# bitsClassicEdit.net
KiCad netlist of a schematic drawn in EAGLE
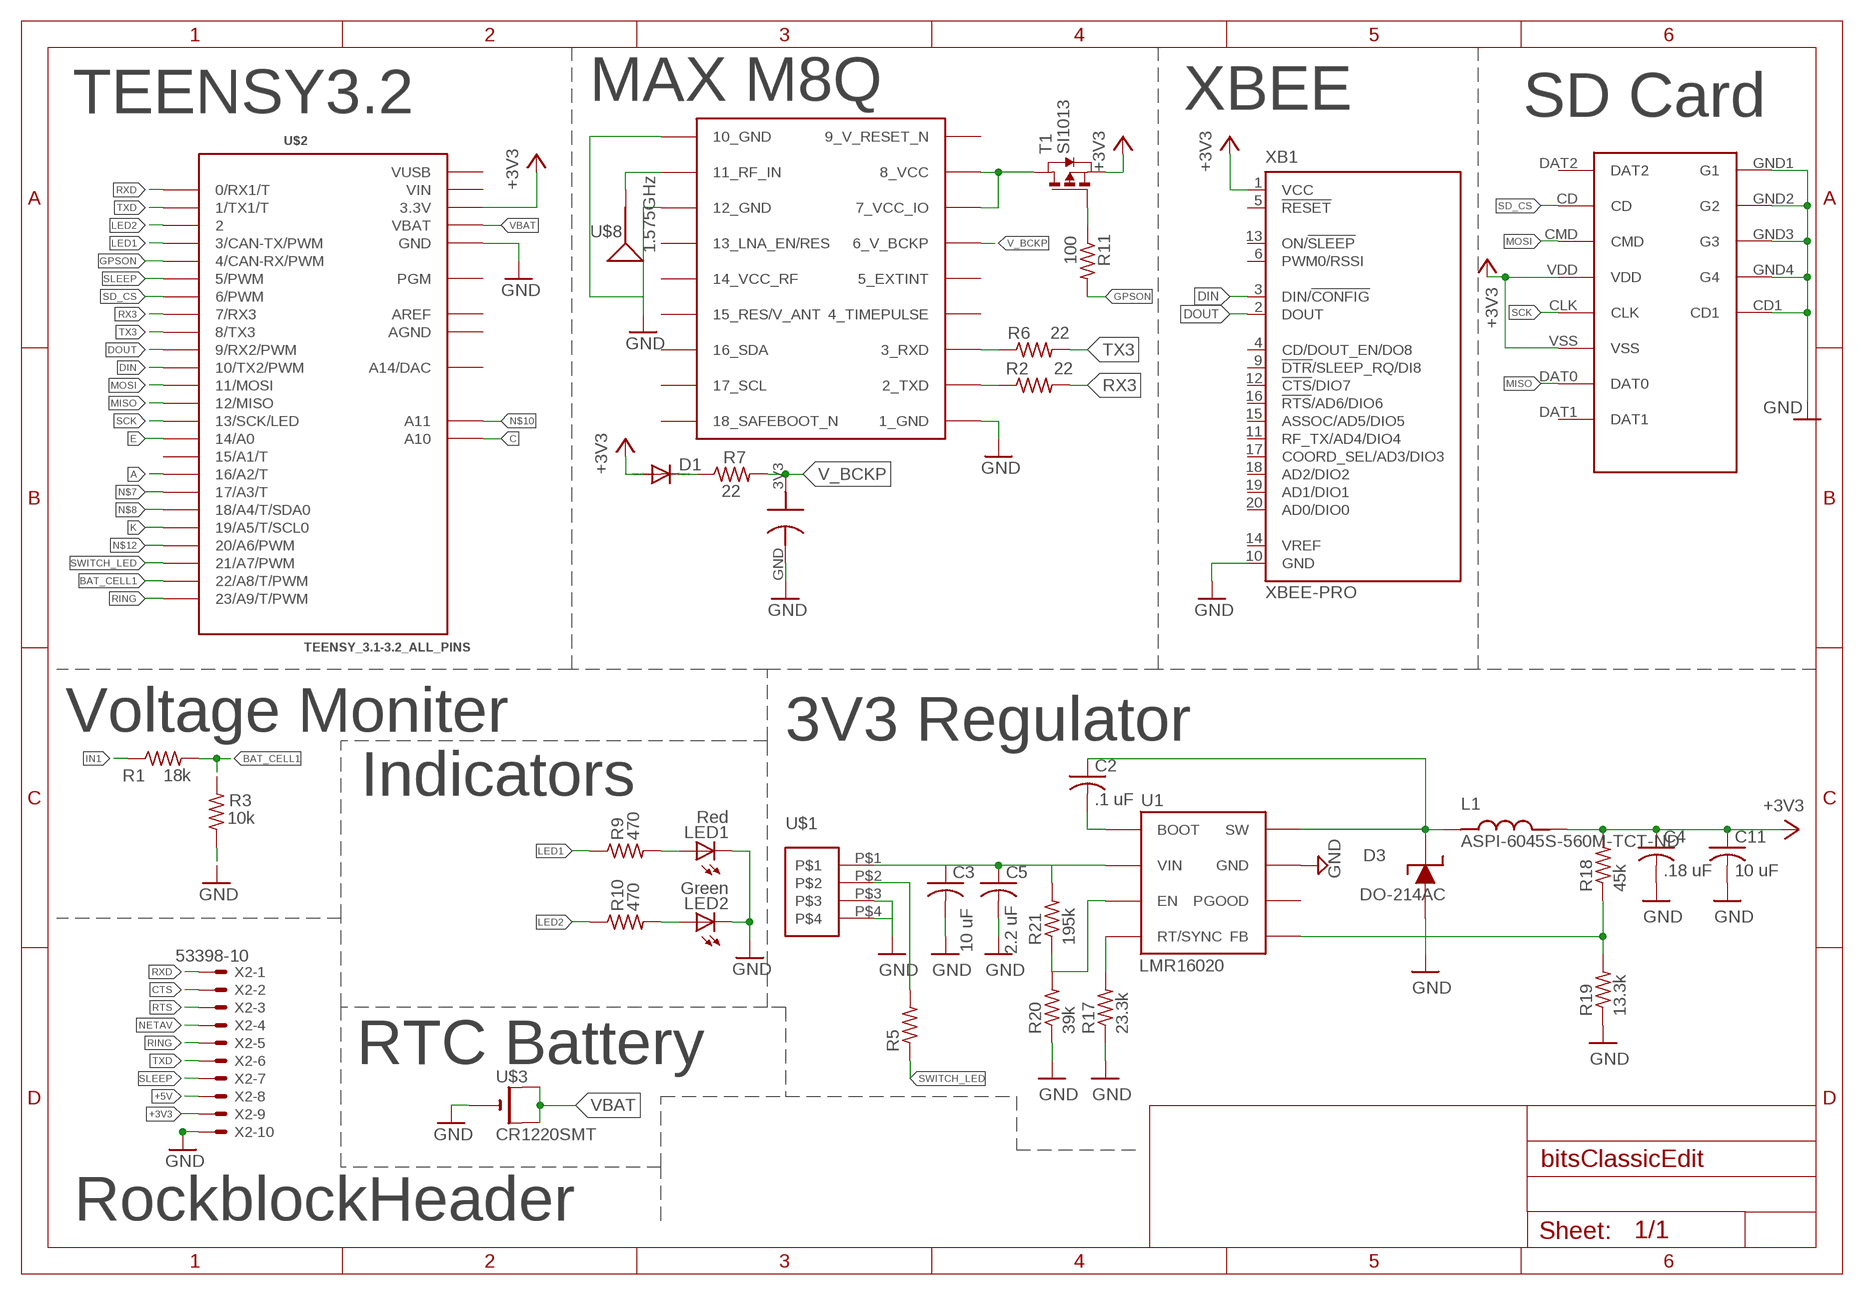
[diagram p0: schematic, sheet 1]

(export (version "E")
  (design (tool "Eeschema 10.0.6"))
  (components
    (comp (ref "C1")
      (value "DCK-3R3E204T614-E")
      (footprint "eagle-import:ELNASUPERCAP")
      (libsource (lib "eagle-import") (part "DCK-3R3E204T614-E"))
    )
    (comp (ref "C2")
      (value ".1 uF")
      (footprint "eagle-import:C0603")
      (libsource (lib "eagle-import") (part "C-USC0603"))
    )
    (comp (ref "C3")
      (value "10 uF")
      (footprint "eagle-import:C1210")
      (libsource (lib "eagle-import") (part "C-USC1210"))
    )
    (comp (ref "C4")
      (value ".18 uF")
      (footprint "eagle-import:C0603")
      (libsource (lib "eagle-import") (part "C-USC0603"))
    )
    (comp (ref "C5")
      (value "2.2 uF")
      (footprint "eagle-import:C1210")
      (libsource (lib "eagle-import") (part "C-USC1210"))
    )
    (comp (ref "C11")
      (value "10 uF")
      (footprint "eagle-import:C0603")
      (libsource (lib "eagle-import") (part "C-USC0603"))
    )
    (comp (ref "D1")
      (value "DIODE-SOD523")
      (footprint "eagle-import:SOD523")
      (libsource (lib "eagle-import") (part "DIODE-SOD523"))
    )
    (comp (ref "D3")
      (value "DO-214AC")
      (footprint "eagle-import:DO-214AC")
      (libsource (lib "eagle-import") (part "DO-214AC"))
    )
    (comp (ref "L1")
      (value "ASPI-6045S-560M-TCT-ND")
      (footprint "eagle-import:ABRACON")
      (libsource (lib "eagle-import") (part "ASPI-6045S-560M-TCT-ND"))
    )
    (comp (ref "LED1")
      (value "Red")
      (footprint "eagle-import:CHIP-LED0603")
      (libsource (lib "eagle-import") (part "LEDCHIP-LED0603"))
    )
    (comp (ref "LED2")
      (value "Green")
      (footprint "eagle-import:CHIP-LED0603")
      (libsource (lib "eagle-import") (part "LEDCHIP-LED0603"))
    )
    (comp (ref "R1")
      (value "18k")
      (footprint "eagle-import:R0603")
      (libsource (lib "eagle-import") (part "resistor_R-US_R0603"))
    )
    (comp (ref "R2")
      (value "22")
      (footprint "eagle-import:R0603")
      (libsource (lib "eagle-import") (part "R-US_R0603"))
    )
    (comp (ref "R3")
      (value "10k")
      (footprint "eagle-import:R0603")
      (libsource (lib "eagle-import") (part "resistor_R-US_R0603"))
    )
    (comp (ref "R5")
      (value "R-US_R0603")
      (footprint "eagle-import:R0603")
      (libsource (lib "eagle-import") (part "resistor_R-US_R0603"))
    )
    (comp (ref "R6")
      (value "22")
      (footprint "eagle-import:R0603")
      (libsource (lib "eagle-import") (part "R-US_R0603"))
    )
    (comp (ref "R7")
      (value "22")
      (footprint "eagle-import:R0603")
      (libsource (lib "eagle-import") (part "R-US_R0603"))
    )
    (comp (ref "R9")
      (value "470")
      (footprint "eagle-import:R0603")
      (libsource (lib "eagle-import") (part "resistor_R-US_R0603"))
    )
    (comp (ref "R10")
      (value "470")
      (footprint "eagle-import:R0603")
      (libsource (lib "eagle-import") (part "resistor_R-US_R0603"))
    )
    (comp (ref "R11")
      (value "100")
      (footprint "eagle-import:R0603")
      (libsource (lib "eagle-import") (part "R-US_R0603"))
    )
    (comp (ref "R17")
      (value "23.3k")
      (footprint "eagle-import:R0603")
      (libsource (lib "eagle-import") (part "resistor_R-US_R0603"))
    )
    (comp (ref "R18")
      (value "45k")
      (footprint "eagle-import:R0603")
      (libsource (lib "eagle-import") (part "resistor_R-US_R0603"))
    )
    (comp (ref "R19")
      (value "13.3k")
      (footprint "eagle-import:R0603")
      (libsource (lib "eagle-import") (part "resistor_R-US_R0603"))
    )
    (comp (ref "R20")
      (value "39k")
      (footprint "eagle-import:R0603")
      (libsource (lib "eagle-import") (part "resistor_R-US_R0603"))
    )
    (comp (ref "R21")
      (value "195k")
      (footprint "eagle-import:R0603")
      (libsource (lib "eagle-import") (part "resistor_R-US_R0603"))
    )
    (comp (ref "T1")
      (value "SI1013")
      (footprint "eagle-import:SC-75")
      (libsource (lib "eagle-import") (part "SI1013"))
    )
    (comp (ref "U$1")
      (value "MICROCLASP_4")
      (footprint "eagle-import:4_PIN_MICROCLASP")
      (libsource (lib "eagle-import") (part "MICROCLASP_4"))
    )
    (comp (ref "U$2")
      (value "TEENSY_3.1-3.2_ALL_PINS")
      (footprint "eagle-import:TEENSY_3.0-3.2&LC_ALL_PINS")
      (libsource (lib "eagle-import") (part "TEENSY_3.1-3.2_ALL_PINS"))
    )
    (comp (ref "U$3")
      (value "CR1220SMT")
      (footprint "eagle-import:CR1220-SMD")
      (libsource (lib "eagle-import") (part "CR1220SMT"))
    )
    (comp (ref "U$4")
      (value "MICRO_SD")
      (footprint "eagle-import:MICRO_SD_HINGED")
      (libsource (lib "eagle-import") (part "MICRO_SD"))
    )
    (comp (ref "U$7")
      (value "MAX-M8")
      (footprint "eagle-import:MAX-M8")
      (libsource (lib "eagle-import") (part "MAX-M8"))
    )
    (comp (ref "U$8")
      (value "1.575GHz")
      (footprint "eagle-import:SPARKFUN-GPS_ANT-GPS-2X7MM")
      (libsource (lib "eagle-import") (part "SPARKFUN-GPS_ANTENNAGPS-2X7MM"))
    )
    (comp (ref "U1")
      (value "LMR16020")
      (footprint "eagle-import:SO8")
      (libsource (lib "eagle-import") (part "LMR16020"))
    )
    (comp (ref "X2")
      (value "53398-10")
      (footprint "eagle-import:53398-10")
      (fields (field (name "MF") "MOLEX") (field (name "MPN") "53398-1071"))
      (libsource (lib "eagle-import") (part "53?-10398"))
    )
    (comp (ref "XB1")
      (value "XBEE-PRO")
      (footprint "eagle-import:XBEE-PRO")
      (fields (field (name "MPN") "XBP24-AWI-001"))
      (libsource (lib "eagle-import") (part "XBEE-PRO"))
    )
  )
  (nets
    (net (code "1") (name "+3V3") (class "Default")
      (node (ref "C11") (pin "1") (pinfunction "1_1") (pintype "passive"))
      (node (ref "C4") (pin "1") (pinfunction "1_1") (pintype "passive"))
      (node (ref "D1") (pin "A") (pinfunction "A_A") (pintype "passive"))
      (node (ref "L1") (pin "P$2") (pinfunction "P$2_P$2") (pintype "bidirectional"))
      (node (ref "R18") (pin "2") (pinfunction "2_2") (pintype "passive"))
      (node (ref "T1") (pin "P$2") (pinfunction "S_P$2") (pintype "passive"))
      (node (ref "U$2") (pin "3.3V") (pinfunction "3.3V_3.3V") (pintype "power_in"))
      (node (ref "U$2") (pin "3.3V1") (pinfunction "3.3V_3.3V1") (pintype "power_in"))
      (node (ref "U$4") (pin "VDD") (pinfunction "VDD_VDD") (pintype "bidirectional"))
      (node (ref "U$4") (pin "VSS") (pinfunction "VSS_VSS") (pintype "bidirectional"))
      (node (ref "X2") (pin "9") (pinfunction "S_9") (pintype "passive"))
      (node (ref "XB1") (pin "1") (pinfunction "VCC_1") (pintype "power_in"))
    )
    (net (code "2") (name "+5V") (class "Default")
      (node (ref "X2") (pin "8") (pinfunction "S_8") (pintype "passive"))
    )
    (net (code "3") (name "/9_V_RESET_N") (class "Default")
      (node (ref "U$7") (pin "9_RESET_N") (pinfunction "9_V_RESET_N_9_RESET_N") (pintype "power_in"))
    )
    (net (code "4") (name "/AGND") (class "Default")
      (node (ref "U$2") (pin "AGND") (pinfunction "AGND_AGND") (pintype "power_in"))
    )
    (net (code "5") (name "/AREF") (class "Default")
      (node (ref "U$2") (pin "AREF") (pinfunction "AREF_AREF") (pintype "power_in"))
    )
    (net (code "6") (name "/VIN") (class "Default")
      (node (ref "U$2") (pin "VIN") (pinfunction "VIN_VIN") (pintype "power_in"))
    )
    (net (code "7") (name "/VUSB") (class "Default")
      (node (ref "U$2") (pin "VUSB") (pinfunction "VUSB_VUSB") (pintype "power_in"))
    )
    (net (code "8") (name "A") (class "Default")
      (node (ref "U$2") (pin "16/A2") (pinfunction "16/A2/T_16/A2") (pintype "bidirectional"))
    )
    (net (code "9") (name "BAT_CELL1") (class "Default")
      (node (ref "R1") (pin "2") (pinfunction "2_2") (pintype "passive"))
      (node (ref "R3") (pin "2") (pinfunction "2_2") (pintype "passive"))
      (node (ref "U$2") (pin "22/A8") (pinfunction "22/A8/T/PWM_22/A8") (pintype "bidirectional"))
    )
    (net (code "10") (name "C") (class "Default")
      (node (ref "U$2") (pin "A10") (pinfunction "A10_A10") (pintype "bidirectional"))
    )
    (net (code "11") (name "CTS") (class "Default")
      (node (ref "X2") (pin "2") (pinfunction "S_2") (pintype "passive"))
    )
    (net (code "12") (name "DIN") (class "Default")
      (node (ref "U$2") (pin "10") (pinfunction "10/TX2/PWM_10") (pintype "bidirectional"))
      (node (ref "XB1") (pin "3") (pinfunction "DIN/~{CONFIG}_3") (pintype "input"))
    )
    (net (code "13") (name "DOUT") (class "Default")
      (node (ref "U$2") (pin "9") (pinfunction "9/RX2/PWM_9") (pintype "bidirectional"))
      (node (ref "XB1") (pin "2") (pinfunction "DOUT_2") (pintype "output"))
    )
    (net (code "14") (name "E") (class "Default")
      (node (ref "U$2") (pin "14/A0") (pinfunction "14/A0_14/A0") (pintype "bidirectional"))
    )
    (net (code "15") (name "GND") (class "Default")
      (node (ref "C1") (pin "GND") (pinfunction "GND_GND") (pintype "bidirectional"))
      (node (ref "C11") (pin "2") (pinfunction "2_2") (pintype "passive"))
      (node (ref "C3") (pin "2") (pinfunction "2_2") (pintype "passive"))
      (node (ref "C4") (pin "2") (pinfunction "2_2") (pintype "passive"))
      (node (ref "C5") (pin "2") (pinfunction "2_2") (pintype "passive"))
      (node (ref "D3") (pin "P$1") (pinfunction "P$1_P$1") (pintype "bidirectional"))
      (node (ref "LED1") (pin "C") (pinfunction "C_C") (pintype "passive"))
      (node (ref "LED2") (pin "C") (pinfunction "C_C") (pintype "passive"))
      (node (ref "R17") (pin "1") (pinfunction "1_1") (pintype "passive"))
      (node (ref "R19") (pin "1") (pinfunction "1_1") (pintype "passive"))
      (node (ref "R20") (pin "1") (pinfunction "1_1") (pintype "passive"))
      (node (ref "R3") (pin "1") (pinfunction "1_1") (pintype "passive"))
      (node (ref "U$1") (pin "P$3") (pinfunction "P$3_P$3") (pintype "bidirectional"))
      (node (ref "U$1") (pin "P$4") (pinfunction "P$4_P$4") (pintype "bidirectional"))
      (node (ref "U$2") (pin "GND") (pinfunction "GND_GND") (pintype "power_in"))
      (node (ref "U$2") (pin "GND1") (pinfunction "GND_GND1") (pintype "power_in"))
      (node (ref "U$3") (pin "-") (pinfunction "-_-") (pintype "passive"))
      (node (ref "U$4") (pin "CD1") (pinfunction "CD1_CD1") (pintype "bidirectional"))
      (node (ref "U$4") (pin "GND1") (pinfunction "G1_GND1") (pintype "bidirectional"))
      (node (ref "U$4") (pin "GND2") (pinfunction "G2_GND2") (pintype "bidirectional"))
      (node (ref "U$4") (pin "GND3") (pinfunction "G3_GND3") (pintype "bidirectional"))
      (node (ref "U$4") (pin "GND4") (pinfunction "G4_GND4") (pintype "bidirectional"))
      (node (ref "U$7") (pin "10_GND") (pinfunction "10_GND_10_GND") (pintype "power_in"))
      (node (ref "U$7") (pin "12_GND") (pinfunction "12_GND_12_GND") (pintype "power_in"))
      (node (ref "U$7") (pin "1_GND") (pinfunction "1_GND_1_GND") (pintype "power_in"))
      (node (ref "U1") (pin "P$7") (pinfunction "GND_P$7") (pintype "bidirectional"))
      (node (ref "U1") (pin "PAD") (pinfunction "GND_PAD") (pintype "bidirectional"))
      (node (ref "X2") (pin "10") (pinfunction "S_10") (pintype "passive"))
      (node (ref "XB1") (pin "10") (pinfunction "GND_10") (pintype "power_in"))
    )
    (net (code "16") (name "GPSON") (class "Default")
      (node (ref "R11") (pin "2") (pinfunction "2_2") (pintype "passive"))
      (node (ref "U$2") (pin "4") (pinfunction "4/CAN-RX/PWM_4") (pintype "bidirectional"))
    )
    (net (code "17") (name "IN1") (class "Default")
      (node (ref "C3") (pin "1") (pinfunction "1_1") (pintype "passive"))
      (node (ref "C5") (pin "1") (pinfunction "1_1") (pintype "passive"))
      (node (ref "R1") (pin "1") (pinfunction "1_1") (pintype "passive"))
      (node (ref "R21") (pin "2") (pinfunction "2_2") (pintype "passive"))
      (node (ref "U$1") (pin "P$1") (pinfunction "P$1_P$1") (pintype "bidirectional"))
      (node (ref "U1") (pin "P$2") (pinfunction "VIN_P$2") (pintype "bidirectional"))
    )
    (net (code "18") (name "K") (class "Default")
      (node (ref "U$2") (pin "19/A5") (pinfunction "19/A5/T/SCL0_19/A5") (pintype "bidirectional"))
    )
    (net (code "19") (name "LED1") (class "Default")
      (node (ref "R9") (pin "1") (pinfunction "1_1") (pintype "passive"))
      (node (ref "U$2") (pin "3") (pinfunction "3/CAN-TX/PWM_3") (pintype "bidirectional"))
    )
    (net (code "20") (name "LED2") (class "Default")
      (node (ref "R10") (pin "1") (pinfunction "1_1") (pintype "passive"))
      (node (ref "U$2") (pin "2") (pinfunction "2_2") (pintype "bidirectional"))
    )
    (net (code "21") (name "MISO") (class "Default")
      (node (ref "U$2") (pin "12") (pinfunction "12/MISO_12") (pintype "bidirectional"))
      (node (ref "U$4") (pin "DAT0") (pinfunction "DAT0_DAT0") (pintype "bidirectional"))
    )
    (net (code "22") (name "MOSI") (class "Default")
      (node (ref "U$2") (pin "11") (pinfunction "11/MOSI_11") (pintype "bidirectional"))
      (node (ref "U$4") (pin "CMD") (pinfunction "CMD_CMD") (pintype "bidirectional"))
    )
    (net (code "23") (name "N$7") (class "Default")
      (node (ref "U$2") (pin "17/A3") (pinfunction "17/A3/T_17/A3") (pintype "bidirectional"))
    )
    (net (code "24") (name "N$8") (class "Default")
      (node (ref "U$2") (pin "18/A4") (pinfunction "18/A4/T/SDA0_18/A4") (pintype "bidirectional"))
    )
    (net (code "25") (name "N$10") (class "Default")
      (node (ref "U$2") (pin "A11") (pinfunction "A11_A11") (pintype "bidirectional"))
    )
    (net (code "26") (name "N$12") (class "Default")
      (node (ref "U$2") (pin "20/A6") (pinfunction "20/A6/PWM_20/A6") (pintype "bidirectional"))
    )
    (net (code "27") (name "NETAV") (class "Default")
      (node (ref "X2") (pin "4") (pinfunction "S_4") (pintype "passive"))
    )
    (net (code "28") (name "Net-(D1-PadC)") (class "Default")
      (node (ref "D1") (pin "C") (pinfunction "C_C") (pintype "passive"))
      (node (ref "R7") (pin "1") (pinfunction "1_1") (pintype "passive"))
    )
    (net (code "29") (name "Net-(LED1-PadA)") (class "Default")
      (node (ref "LED1") (pin "A") (pinfunction "A_A") (pintype "passive"))
      (node (ref "R9") (pin "2") (pinfunction "2_2") (pintype "passive"))
    )
    (net (code "30") (name "Net-(LED2-PadA)") (class "Default")
      (node (ref "LED2") (pin "A") (pinfunction "A_A") (pintype "passive"))
      (node (ref "R10") (pin "2") (pinfunction "2_2") (pintype "passive"))
    )
    (net (code "31") (name "Net-(R2-Pad1)") (class "Default")
      (node (ref "R2") (pin "1") (pinfunction "1_1") (pintype "passive"))
      (node (ref "U$7") (pin "2_TXD") (pinfunction "2_TXD_2_TXD") (pintype "bidirectional"))
    )
    (net (code "32") (name "Net-(R5-Pad2)") (class "Default")
      (node (ref "R5") (pin "2") (pinfunction "2_2") (pintype "passive"))
      (node (ref "U$1") (pin "P$2") (pinfunction "P$2_P$2") (pintype "bidirectional"))
    )
    (net (code "33") (name "Net-(R6-Pad1)") (class "Default")
      (node (ref "R6") (pin "1") (pinfunction "1_1") (pintype "passive"))
      (node (ref "U$7") (pin "3_RXD") (pinfunction "3_RXD_3_RXD") (pintype "bidirectional"))
    )
    (net (code "34") (name "Net-(T1-D)") (class "Default")
      (node (ref "T1") (pin "P$3") (pinfunction "D_P$3") (pintype "passive"))
      (node (ref "U$7") (pin "7_VCC_IO") (pinfunction "7_VCC_IO_7_VCC_IO") (pintype "power_in"))
      (node (ref "U$7") (pin "8_VCC") (pinfunction "8_VCC_8_VCC") (pintype "power_in"))
    )
    (net (code "35") (name "Net-(T1-G)") (class "Default")
      (node (ref "R11") (pin "1") (pinfunction "1_1") (pintype "passive"))
      (node (ref "T1") (pin "P$1") (pinfunction "G_P$1") (pintype "passive"))
    )
    (net (code "36") (name "Net-(U$8-SIGNAL)") (class "Default")
      (node (ref "U$7") (pin "11_RF_IN") (pinfunction "11_RF_IN_11_RF_IN") (pintype "bidirectional"))
      (node (ref "U$8") (pin "1") (pinfunction "SIGNAL_1") (pintype "bidirectional"))
    )
    (net (code "37") (name "Net-(U1-BOOT)") (class "Default")
      (node (ref "C2") (pin "2") (pinfunction "2_2") (pintype "passive"))
      (node (ref "U1") (pin "P$1") (pinfunction "BOOT_P$1") (pintype "bidirectional"))
    )
    (net (code "38") (name "Net-(U1-EN)") (class "Default")
      (node (ref "R20") (pin "2") (pinfunction "2_2") (pintype "passive"))
      (node (ref "R21") (pin "1") (pinfunction "1_1") (pintype "passive"))
      (node (ref "U1") (pin "P$3") (pinfunction "EN_P$3") (pintype "bidirectional"))
    )
    (net (code "39") (name "Net-(U1-FB)") (class "Default")
      (node (ref "R18") (pin "1") (pinfunction "1_1") (pintype "passive"))
      (node (ref "R19") (pin "2") (pinfunction "2_2") (pintype "passive"))
      (node (ref "U1") (pin "P$5") (pinfunction "FB_P$5") (pintype "bidirectional"))
    )
    (net (code "40") (name "Net-(U1-RT{slash}SYNC)") (class "Default")
      (node (ref "R17") (pin "2") (pinfunction "2_2") (pintype "passive"))
      (node (ref "U1") (pin "P$4") (pinfunction "RT/SYNC_P$4") (pintype "bidirectional"))
    )
    (net (code "41") (name "Net-(U1-SW)") (class "Default")
      (node (ref "C2") (pin "1") (pinfunction "1_1") (pintype "passive"))
      (node (ref "D3") (pin "P$2") (pinfunction "P$2_P$2") (pintype "bidirectional"))
      (node (ref "L1") (pin "P$1") (pinfunction "P$1_P$1") (pintype "bidirectional"))
      (node (ref "U1") (pin "P$8") (pinfunction "SW_P$8") (pintype "bidirectional"))
    )
    (net (code "42") (name "RING") (class "Default")
      (node (ref "U$2") (pin "23/A9") (pinfunction "23/A9/T/PWM_23/A9") (pintype "bidirectional"))
      (node (ref "X2") (pin "5") (pinfunction "S_5") (pintype "passive"))
    )
    (net (code "43") (name "RTS") (class "Default")
      (node (ref "X2") (pin "3") (pinfunction "S_3") (pintype "passive"))
    )
    (net (code "44") (name "RX3") (class "Default")
      (node (ref "R2") (pin "2") (pinfunction "2_2") (pintype "passive"))
      (node (ref "U$2") (pin "7") (pinfunction "7/RX3_7") (pintype "bidirectional"))
    )
    (net (code "45") (name "RXD") (class "Default")
      (node (ref "U$2") (pin "0") (pinfunction "0/RX1/T_0") (pintype "bidirectional"))
      (node (ref "X2") (pin "1") (pinfunction "S_1") (pintype "passive"))
    )
    (net (code "46") (name "SCK") (class "Default")
      (node (ref "U$2") (pin "13") (pinfunction "13/SCK/LED_13") (pintype "bidirectional"))
      (node (ref "U$4") (pin "CLK") (pinfunction "CLK_CLK") (pintype "bidirectional"))
    )
    (net (code "47") (name "SD_CS") (class "Default")
      (node (ref "U$2") (pin "6") (pinfunction "6/PWM_6") (pintype "bidirectional"))
      (node (ref "U$4") (pin "CD") (pinfunction "CD_CD") (pintype "bidirectional"))
    )
    (net (code "48") (name "SLEEP") (class "Default")
      (node (ref "U$2") (pin "5") (pinfunction "5/PWM_5") (pintype "bidirectional"))
      (node (ref "X2") (pin "7") (pinfunction "S_7") (pintype "passive"))
    )
    (net (code "49") (name "SWITCH_LED") (class "Default")
      (node (ref "R5") (pin "1") (pinfunction "1_1") (pintype "passive"))
      (node (ref "U$2") (pin "21/A7") (pinfunction "21/A7/PWM_21/A7") (pintype "bidirectional"))
    )
    (net (code "50") (name "TX3") (class "Default")
      (node (ref "R6") (pin "2") (pinfunction "2_2") (pintype "passive"))
      (node (ref "U$2") (pin "8") (pinfunction "8/TX3_8") (pintype "bidirectional"))
    )
    (net (code "51") (name "TXD") (class "Default")
      (node (ref "U$2") (pin "1") (pinfunction "1/TX1/T_1") (pintype "bidirectional"))
      (node (ref "X2") (pin "6") (pinfunction "S_6") (pintype "passive"))
    )
    (net (code "52") (name "VBAT") (class "Default")
      (node (ref "U$2") (pin "VBAT") (pinfunction "VBAT_VBAT") (pintype "power_in"))
      (node (ref "U$3") (pin "+$1") (pinfunction "+_+$1") (pintype "passive"))
      (node (ref "U$3") (pin "+$2") (pinfunction "+1_+$2") (pintype "passive"))
    )
    (net (code "53") (name "V_BCKP") (class "Default")
      (node (ref "C1") (pin "3V3") (pinfunction "3V3_3V3") (pintype "bidirectional"))
      (node (ref "R7") (pin "2") (pinfunction "2_2") (pintype "passive"))
      (node (ref "U$7") (pin "6_V_BCKP") (pinfunction "6_V_BCKP_6_V_BCKP") (pintype "bidirectional"))
    )
    (net (code "54") (name "unconnected-(U$2-15{slash}A1{slash}T-Pad15{slash}A1)") (class "Default")
      (node (ref "U$2") (pin "15/A1") (pinfunction "15/A1/T_15/A1") (pintype "bidirectional"))
    )
    (net (code "55") (name "unconnected-(U$2-A14{slash}DAC-PadRESET{slash}DAC)") (class "Default")
      (node (ref "U$2") (pin "RESET/DAC") (pinfunction "A14/DAC_RESET/DAC") (pintype "bidirectional"))
    )
    (net (code "56") (name "unconnected-(U$2-PadPGM)") (class "Default")
      (node (ref "U$2") (pin "PGM") (pinfunction "PGM_PGM") (pintype "bidirectional"))
    )
    (net (code "57") (name "unconnected-(U$4-PadDAT1)") (class "Default")
      (node (ref "U$4") (pin "DAT1") (pinfunction "DAT1_DAT1") (pintype "bidirectional"))
    )
    (net (code "58") (name "unconnected-(U$4-PadDAT2)") (class "Default")
      (node (ref "U$4") (pin "DAT2") (pinfunction "DAT2_DAT2") (pintype "bidirectional"))
    )
    (net (code "59") (name "unconnected-(U$7-13_LNA_EN{slash}RES-Pad13_LNA_EN)") (class "Default")
      (node (ref "U$7") (pin "13_LNA_EN") (pinfunction "13_LNA_EN/RES_13_LNA_EN") (pintype "bidirectional"))
    )
    (net (code "60") (name "unconnected-(U$7-15_RES{slash}V_ANT-Pad15_V_ANT{slash}RESERVED)") (class "Default")
      (node (ref "U$7") (pin "15_V_ANT/RESERVED") (pinfunction "15_RES/V_ANT_15_V_ANT/RESERVED") (pintype "bidirectional"))
    )
    (net (code "61") (name "unconnected-(U$7-Pad4_TIMEPULSE)") (class "Default")
      (node (ref "U$7") (pin "4_TIMEPULSE") (pinfunction "4_TIMEPULSE_4_TIMEPULSE") (pintype "bidirectional"))
    )
    (net (code "62") (name "unconnected-(U$7-Pad5_EXTINT)") (class "Default")
      (node (ref "U$7") (pin "5_EXTINT") (pinfunction "5_EXTINT_5_EXTINT") (pintype "bidirectional"))
    )
    (net (code "63") (name "unconnected-(U$7-Pad14_VCC_RF)") (class "Default")
      (node (ref "U$7") (pin "14_VCC_RF") (pinfunction "14_VCC_RF_14_VCC_RF") (pintype "bidirectional"))
    )
    (net (code "64") (name "unconnected-(U$7-Pad16_SDA)") (class "Default")
      (node (ref "U$7") (pin "16_SDA") (pinfunction "16_SDA_16_SDA") (pintype "bidirectional"))
    )
    (net (code "65") (name "unconnected-(U$7-Pad17_SCL)") (class "Default")
      (node (ref "U$7") (pin "17_SCL") (pinfunction "17_SCL_17_SCL") (pintype "bidirectional"))
    )
    (net (code "66") (name "unconnected-(U$7-Pad18_SAFEBOOT_N)") (class "Default")
      (node (ref "U$7") (pin "18_SAFEBOOT_N") (pinfunction "18_SAFEBOOT_N_18_SAFEBOOT_N") (pintype "bidirectional"))
    )
    (net (code "67") (name "unconnected-(U1-PGOOD-PadP$6)") (class "Default")
      (node (ref "U1") (pin "P$6") (pinfunction "PGOOD_P$6") (pintype "bidirectional"))
    )
    (net (code "68") (name "unconnected-(XB1-AD0{slash}DIO0-Pad20)") (class "Default")
      (node (ref "XB1") (pin "20") (pinfunction "AD0/DIO0_20") (pintype "bidirectional"))
    )
    (net (code "69") (name "unconnected-(XB1-AD1{slash}DIO1-Pad19)") (class "Default")
      (node (ref "XB1") (pin "19") (pinfunction "AD1/DIO1_19") (pintype "bidirectional"))
    )
    (net (code "70") (name "unconnected-(XB1-AD2{slash}DIO2-Pad18)") (class "Default")
      (node (ref "XB1") (pin "18") (pinfunction "AD2/DIO2_18") (pintype "bidirectional"))
    )
    (net (code "71") (name "unconnected-(XB1-ASSOC{slash}AD5{slash}DIO5-Pad15)") (class "Default")
      (node (ref "XB1") (pin "15") (pinfunction "ASSOC/AD5/DIO5_15") (pintype "bidirectional"))
    )
    (net (code "72") (name "unconnected-(XB1-CD{slash}DOUT_EN{slash}DO8-Pad4)") (class "Default")
      (node (ref "XB1") (pin "4") (pinfunction "CD/DOUT_EN/DO8_4") (pintype "output"))
    )
    (net (code "73") (name "unconnected-(XB1-COORD_SEL{slash}AD3{slash}DIO3-Pad17)") (class "Default")
      (node (ref "XB1") (pin "17") (pinfunction "COORD_SEL/AD3/DIO3_17") (pintype "bidirectional"))
    )
    (net (code "74") (name "unconnected-(XB1-ON{slash}~{SLEEP}-Pad13)") (class "Default")
      (node (ref "XB1") (pin "13") (pinfunction "ON/~{SLEEP}_13") (pintype "output"))
    )
    (net (code "75") (name "unconnected-(XB1-PWM0{slash}RSSI-Pad6)") (class "Default")
      (node (ref "XB1") (pin "6") (pinfunction "PWM0/RSSI_6") (pintype "output"))
    )
    (net (code "76") (name "unconnected-(XB1-RF_TX{slash}AD4{slash}DIO4-Pad11)") (class "Default")
      (node (ref "XB1") (pin "11") (pinfunction "RF_TX/AD4/DIO4_11") (pintype "bidirectional"))
    )
    (net (code "77") (name "unconnected-(XB1-VREF-Pad14)") (class "Default")
      (node (ref "XB1") (pin "14") (pinfunction "VREF_14") (pintype "input"))
    )
    (net (code "78") (name "unconnected-(XB1-~{CTS}{slash}DIO7-Pad12)") (class "Default")
      (node (ref "XB1") (pin "12") (pinfunction "~{CTS}/DIO7_12") (pintype "bidirectional"))
    )
    (net (code "79") (name "unconnected-(XB1-~{DTR}{slash}SLEEP_RQ{slash}DI8-Pad9)") (class "Default")
      (node (ref "XB1") (pin "9") (pinfunction "~{DTR}/SLEEP_RQ/DI8_9") (pintype "bidirectional"))
    )
    (net (code "80") (name "unconnected-(XB1-~{RESET}-Pad5)") (class "Default")
      (node (ref "XB1") (pin "5") (pinfunction "~{RESET}_5") (pintype "input"))
    )
    (net (code "81") (name "unconnected-(XB1-~{RTS}{slash}AD6{slash}DIO6-Pad16)") (class "Default")
      (node (ref "XB1") (pin "16") (pinfunction "~{RTS}/AD6/DIO6_16") (pintype "bidirectional"))
    )
  )
)
